# TommyPROM-uno.net
KiCad netlist of a schematic drawn in EAGLE
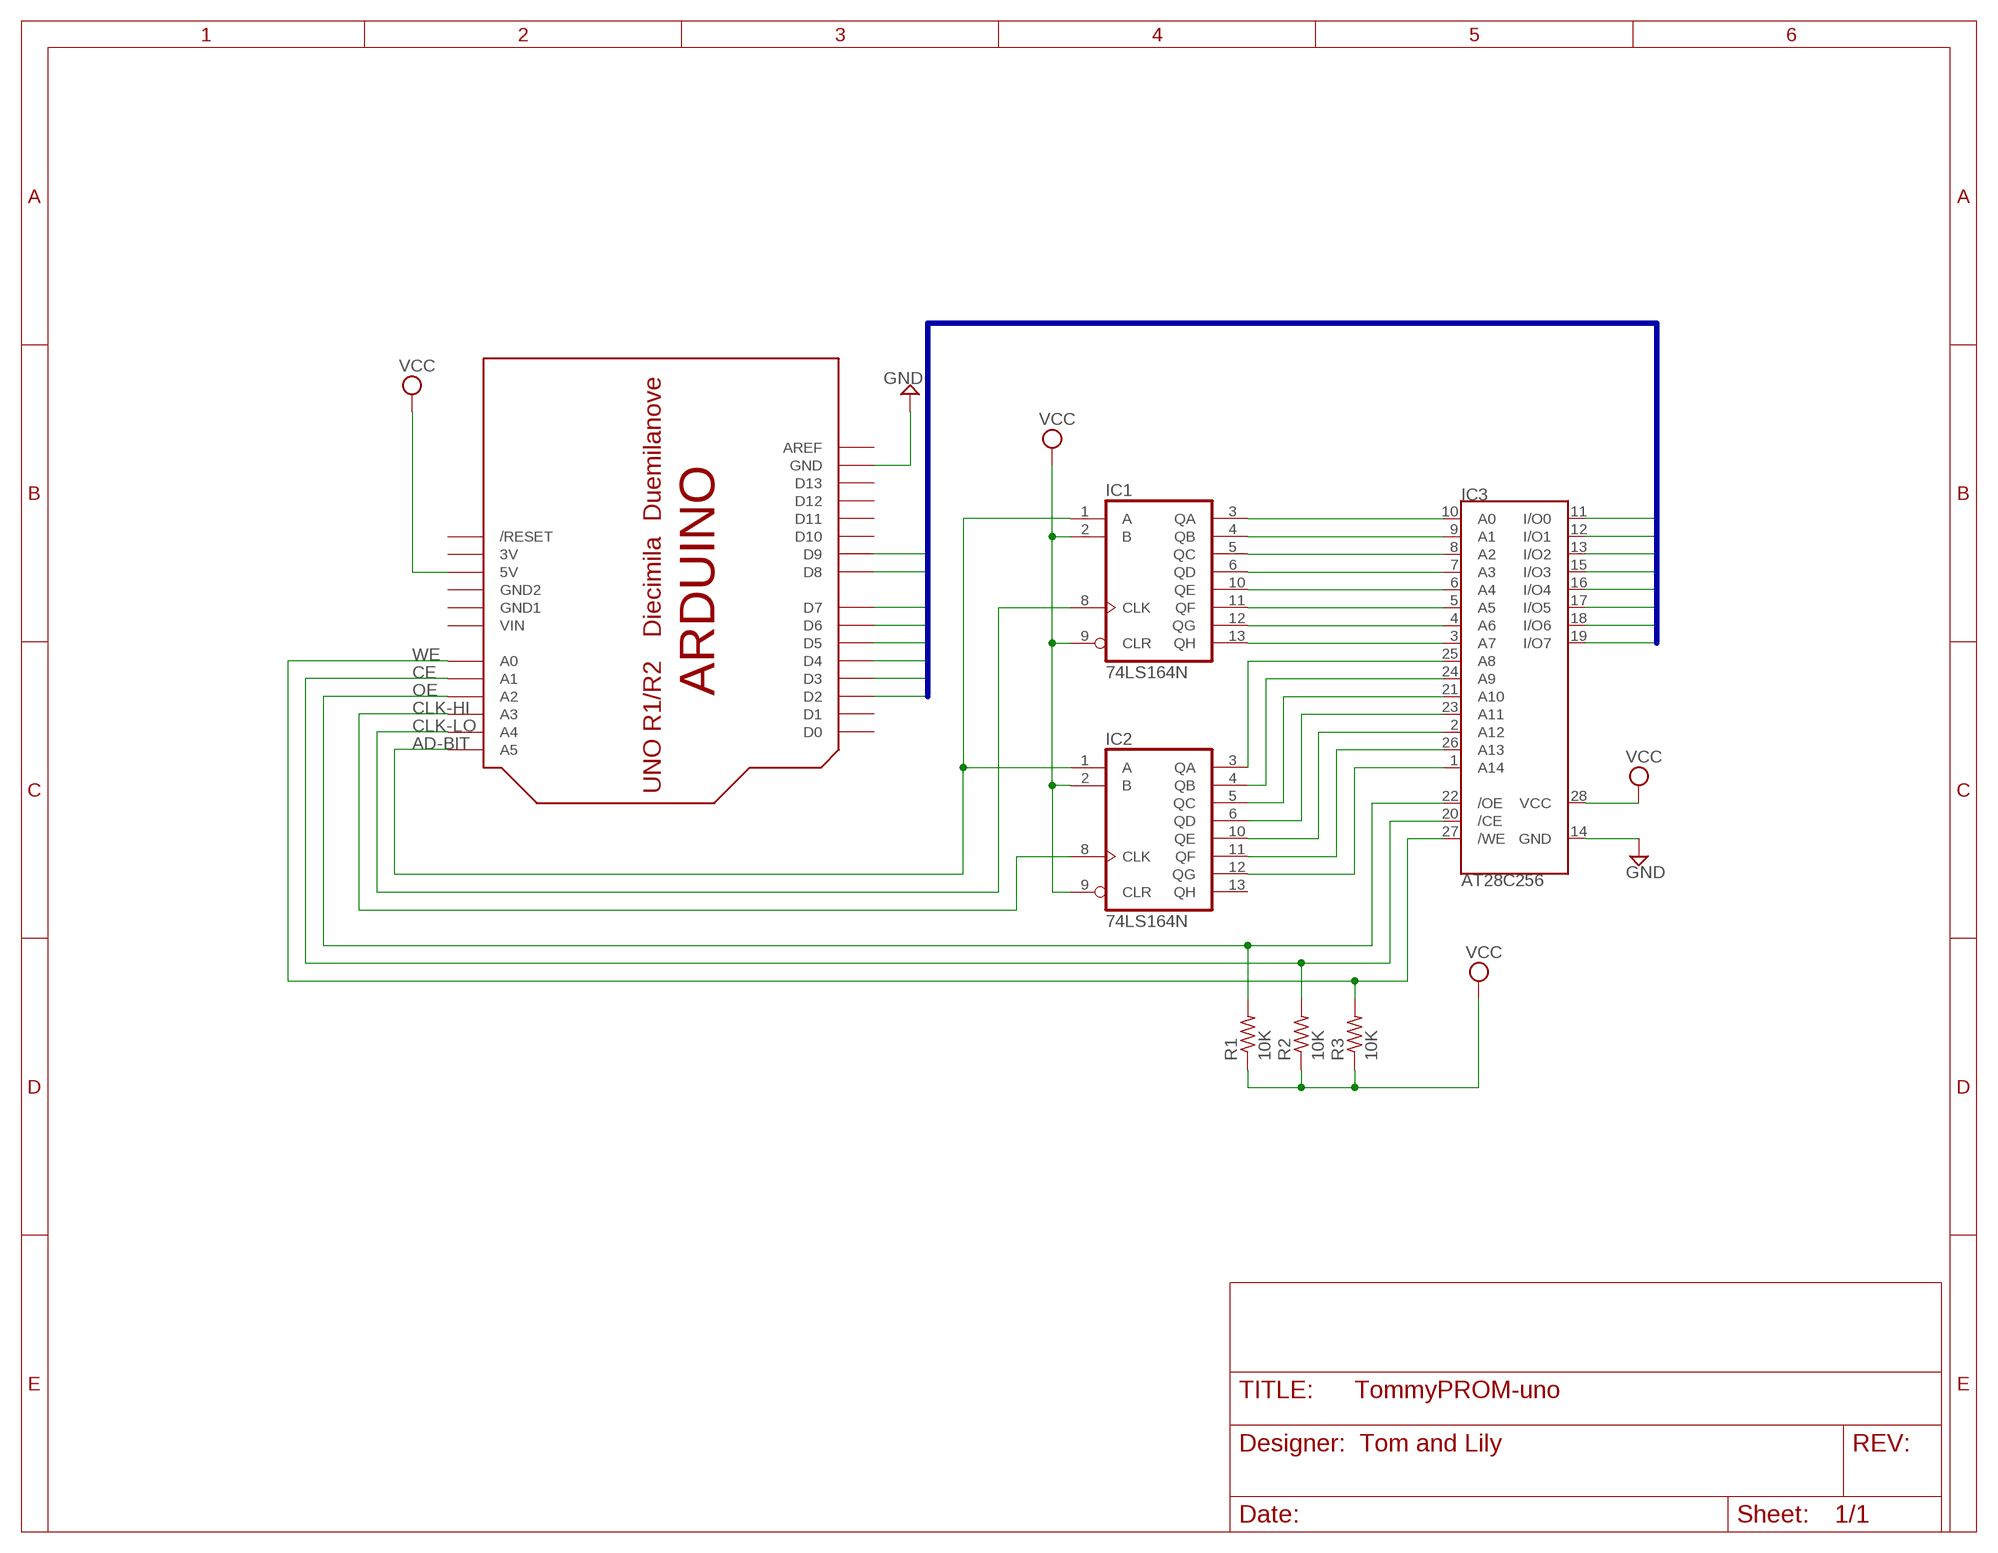
[diagram p0: schematic, sheet 1]

(export (version "E")
  (design (tool "Eeschema 10.0.6"))
  (components
    (comp (ref "IC1")
      (value "74LS164N")
      (footprint "eagle-import:DIL14")
      (libsource (lib "eagle-import") (part "74164NLS"))
    )
    (comp (ref "IC2")
      (value "74LS164N")
      (footprint "eagle-import:DIL14")
      (libsource (lib "eagle-import") (part "74164NLS"))
    )
    (comp (ref "IC3")
      (value "AT28C256")
      (footprint "eagle-import:DIL28-6")
      (libsource (lib "eagle-import") (part "AT28C256-28DIP"))
    )
    (comp (ref "R1")
      (value "10K")
      (footprint "eagle-import:0204_5")
      (libsource (lib "eagle-import") (part "R-US_0204/5"))
    )
    (comp (ref "R2")
      (value "10K")
      (footprint "eagle-import:0204_5")
      (libsource (lib "eagle-import") (part "R-US_0204/5"))
    )
    (comp (ref "R3")
      (value "10K")
      (footprint "eagle-import:0204_5")
      (libsource (lib "eagle-import") (part "R-US_0204/5"))
    )
    (comp (ref "U$1")
      (value "ARDUINO-BPLACE")
      (footprint "eagle-import:ARDUINO-BPLACE")
      (libsource (lib "eagle-import") (part "ARDUINO-BPLACE"))
    )
  )
  (nets
    (net (code "1") (name "/3V") (class "Default")
      (node (ref "U$1") (pin "3V") (pinfunction "3V_3V") (pintype "power_in"))
    )
    (net (code "2") (name "/AD-BIT") (class "Default")
      (node (ref "IC1") (pin "1") (pinfunction "A_1") (pintype "input"))
      (node (ref "IC2") (pin "1") (pinfunction "A_1") (pintype "input"))
      (node (ref "U$1") (pin "A5") (pinfunction "A5_A5") (pintype "bidirectional"))
    )
    (net (code "3") (name "/CE") (class "Default")
      (node (ref "IC3") (pin "20") (pinfunction "/CE_20") (pintype "input"))
      (node (ref "R2") (pin "2") (pinfunction "2_2") (pintype "passive"))
      (node (ref "U$1") (pin "A1") (pinfunction "A1_A1") (pintype "bidirectional"))
    )
    (net (code "4") (name "/CLK-HI") (class "Default")
      (node (ref "IC2") (pin "8") (pinfunction "CLK_8") (pintype "input"))
      (node (ref "U$1") (pin "A3") (pinfunction "A3_A3") (pintype "bidirectional"))
    )
    (net (code "5") (name "/CLK-LO") (class "Default")
      (node (ref "IC1") (pin "8") (pinfunction "CLK_8") (pintype "input"))
      (node (ref "U$1") (pin "A4") (pinfunction "A4_A4") (pintype "bidirectional"))
    )
    (net (code "6") (name "/D0") (class "Default")
      (node (ref "IC3") (pin "11") (pinfunction "I/O0_11") (pintype "bidirectional"))
      (node (ref "U$1") (pin "D2") (pinfunction "D2_D2") (pintype "bidirectional"))
    )
    (net (code "7") (name "/D1") (class "Default")
      (node (ref "IC3") (pin "12") (pinfunction "I/O1_12") (pintype "bidirectional"))
      (node (ref "U$1") (pin "D3") (pinfunction "D3_D3") (pintype "bidirectional"))
    )
    (net (code "8") (name "/D2") (class "Default")
      (node (ref "IC3") (pin "13") (pinfunction "I/O2_13") (pintype "bidirectional"))
      (node (ref "U$1") (pin "D4") (pinfunction "D4_D4") (pintype "bidirectional"))
    )
    (net (code "9") (name "/D3") (class "Default")
      (node (ref "IC3") (pin "15") (pinfunction "I/O3_15") (pintype "bidirectional"))
      (node (ref "U$1") (pin "D5") (pinfunction "D5_D5") (pintype "bidirectional"))
    )
    (net (code "10") (name "/D4") (class "Default")
      (node (ref "IC3") (pin "16") (pinfunction "I/O4_16") (pintype "bidirectional"))
      (node (ref "U$1") (pin "D6") (pinfunction "D6_D6") (pintype "bidirectional"))
    )
    (net (code "11") (name "/D5") (class "Default")
      (node (ref "IC3") (pin "17") (pinfunction "I/O5_17") (pintype "bidirectional"))
      (node (ref "U$1") (pin "D7") (pinfunction "D7_D7") (pintype "bidirectional"))
    )
    (net (code "12") (name "/D6") (class "Default")
      (node (ref "IC3") (pin "18") (pinfunction "I/O6_18") (pintype "bidirectional"))
      (node (ref "U$1") (pin "D8") (pinfunction "D8_D8") (pintype "bidirectional"))
    )
    (net (code "13") (name "/D7") (class "Default")
      (node (ref "IC3") (pin "19") (pinfunction "I/O7_19") (pintype "bidirectional"))
      (node (ref "U$1") (pin "D9") (pinfunction "D9_D9") (pintype "bidirectional"))
    )
    (net (code "15") (name "/GND1") (class "Default")
      (node (ref "U$1") (pin "GND1") (pinfunction "GND1_GND1") (pintype "power_in"))
    )
    (net (code "16") (name "/GND2") (class "Default")
      (node (ref "U$1") (pin "GND2") (pinfunction "GND2_GND2") (pintype "power_in"))
    )
    (net (code "17") (name "/OE") (class "Default")
      (node (ref "IC3") (pin "22") (pinfunction "/OE_22") (pintype "input"))
      (node (ref "R1") (pin "2") (pinfunction "2_2") (pintype "passive"))
      (node (ref "U$1") (pin "A2") (pinfunction "A2_A2") (pintype "bidirectional"))
    )
    (net (code "18") (name "/VIN") (class "Default")
      (node (ref "U$1") (pin "VIN") (pinfunction "VIN_VIN") (pintype "power_in"))
    )
    (net (code "19") (name "/WE") (class "Default")
      (node (ref "IC3") (pin "27") (pinfunction "/WE_27") (pintype "input"))
      (node (ref "R3") (pin "2") (pinfunction "2_2") (pintype "passive"))
      (node (ref "U$1") (pin "A0") (pinfunction "A0_A0") (pintype "bidirectional"))
    )
    (net (code "20") (name "GND") (class "Default")
      (node (ref "IC3") (pin "14") (pinfunction "GND_14") (pintype "power_in"))
      (node (ref "U$1") (pin "GND") (pinfunction "GND_GND") (pintype "power_in"))
    )
    (net (code "21") (name "Net-(IC1A-QA)") (class "Default")
      (node (ref "IC1") (pin "3") (pinfunction "QA_3") (pintype "output"))
      (node (ref "IC3") (pin "10") (pinfunction "A0_10") (pintype "input"))
    )
    (net (code "22") (name "Net-(IC1A-QB)") (class "Default")
      (node (ref "IC1") (pin "4") (pinfunction "QB_4") (pintype "output"))
      (node (ref "IC3") (pin "9") (pinfunction "A1_9") (pintype "input"))
    )
    (net (code "23") (name "Net-(IC1A-QC)") (class "Default")
      (node (ref "IC1") (pin "5") (pinfunction "QC_5") (pintype "output"))
      (node (ref "IC3") (pin "8") (pinfunction "A2_8") (pintype "input"))
    )
    (net (code "24") (name "Net-(IC1A-QD)") (class "Default")
      (node (ref "IC1") (pin "6") (pinfunction "QD_6") (pintype "output"))
      (node (ref "IC3") (pin "7") (pinfunction "A3_7") (pintype "input"))
    )
    (net (code "25") (name "Net-(IC1A-QE)") (class "Default")
      (node (ref "IC1") (pin "10") (pinfunction "QE_10") (pintype "output"))
      (node (ref "IC3") (pin "6") (pinfunction "A4_6") (pintype "input"))
    )
    (net (code "26") (name "Net-(IC1A-QF)") (class "Default")
      (node (ref "IC1") (pin "11") (pinfunction "QF_11") (pintype "output"))
      (node (ref "IC3") (pin "5") (pinfunction "A5_5") (pintype "input"))
    )
    (net (code "27") (name "Net-(IC1A-QG)") (class "Default")
      (node (ref "IC1") (pin "12") (pinfunction "QG_12") (pintype "output"))
      (node (ref "IC3") (pin "4") (pinfunction "A6_4") (pintype "input"))
    )
    (net (code "28") (name "Net-(IC1A-QH)") (class "Default")
      (node (ref "IC1") (pin "13") (pinfunction "QH_13") (pintype "output"))
      (node (ref "IC3") (pin "3") (pinfunction "A7_3") (pintype "input"))
    )
    (net (code "29") (name "Net-(IC2A-QA)") (class "Default")
      (node (ref "IC2") (pin "3") (pinfunction "QA_3") (pintype "output"))
      (node (ref "IC3") (pin "25") (pinfunction "A8_25") (pintype "input"))
    )
    (net (code "30") (name "Net-(IC2A-QB)") (class "Default")
      (node (ref "IC2") (pin "4") (pinfunction "QB_4") (pintype "output"))
      (node (ref "IC3") (pin "24") (pinfunction "A9_24") (pintype "input"))
    )
    (net (code "31") (name "Net-(IC2A-QC)") (class "Default")
      (node (ref "IC2") (pin "5") (pinfunction "QC_5") (pintype "output"))
      (node (ref "IC3") (pin "21") (pinfunction "A10_21") (pintype "input"))
    )
    (net (code "32") (name "Net-(IC2A-QD)") (class "Default")
      (node (ref "IC2") (pin "6") (pinfunction "QD_6") (pintype "output"))
      (node (ref "IC3") (pin "23") (pinfunction "A11_23") (pintype "input"))
    )
    (net (code "33") (name "Net-(IC2A-QE)") (class "Default")
      (node (ref "IC2") (pin "10") (pinfunction "QE_10") (pintype "output"))
      (node (ref "IC3") (pin "2") (pinfunction "A12_2") (pintype "input"))
    )
    (net (code "34") (name "Net-(IC2A-QF)") (class "Default")
      (node (ref "IC2") (pin "11") (pinfunction "QF_11") (pintype "output"))
      (node (ref "IC3") (pin "26") (pinfunction "A13_26") (pintype "input"))
    )
    (net (code "35") (name "Net-(IC2A-QG)") (class "Default")
      (node (ref "IC2") (pin "12") (pinfunction "QG_12") (pintype "output"))
      (node (ref "IC3") (pin "1") (pinfunction "A14_1") (pintype "input"))
    )
    (net (code "36") (name "VCC") (class "Default")
      (node (ref "IC1") (pin "2") (pinfunction "B_2") (pintype "input"))
      (node (ref "IC1") (pin "9") (pinfunction "CLR_9") (pintype "input"))
      (node (ref "IC2") (pin "2") (pinfunction "B_2") (pintype "input"))
      (node (ref "IC2") (pin "9") (pinfunction "CLR_9") (pintype "input"))
      (node (ref "IC3") (pin "28") (pinfunction "VCC_28") (pintype "power_in"))
      (node (ref "R1") (pin "1") (pinfunction "1_1") (pintype "passive"))
      (node (ref "R2") (pin "1") (pinfunction "1_1") (pintype "passive"))
      (node (ref "R3") (pin "1") (pinfunction "1_1") (pintype "passive"))
      (node (ref "U$1") (pin "5V") (pinfunction "5V_5V") (pintype "power_in"))
    )
    (net (code "37") (name "unconnected-(IC2A-QH-Pad13)") (class "Default")
      (node (ref "IC2") (pin "13") (pinfunction "QH_13") (pintype "output"))
    )
    (net (code "38") (name "unconnected-(U$1-PadAREF)") (class "Default")
      (node (ref "U$1") (pin "AREF") (pinfunction "AREF_AREF") (pintype "bidirectional"))
    )
    (net (code "39") (name "unconnected-(U$1-PadD0)") (class "Default")
      (node (ref "U$1") (pin "D0") (pinfunction "D0_D0") (pintype "bidirectional"))
    )
    (net (code "40") (name "unconnected-(U$1-PadD1)") (class "Default")
      (node (ref "U$1") (pin "D1") (pinfunction "D1_D1") (pintype "bidirectional"))
    )
    (net (code "41") (name "unconnected-(U$1-PadD10)") (class "Default")
      (node (ref "U$1") (pin "D10") (pinfunction "D10_D10") (pintype "bidirectional"))
    )
    (net (code "42") (name "unconnected-(U$1-PadD11)") (class "Default")
      (node (ref "U$1") (pin "D11") (pinfunction "D11_D11") (pintype "bidirectional"))
    )
    (net (code "43") (name "unconnected-(U$1-PadD12)") (class "Default")
      (node (ref "U$1") (pin "D12") (pinfunction "D12_D12") (pintype "bidirectional"))
    )
    (net (code "44") (name "unconnected-(U$1-PadD13)") (class "Default")
      (node (ref "U$1") (pin "D13") (pinfunction "D13_D13") (pintype "bidirectional"))
    )
    (net (code "45") (name "unconnected-(U$1-{slash}RESET-PadRESET)") (class "Default")
      (node (ref "U$1") (pin "RESET") (pinfunction "/RESET_RESET") (pintype "bidirectional"))
    )
  )
)
